# Golden_arduino_Updated.net
KiCad netlist of a schematic drawn in Altium Designer
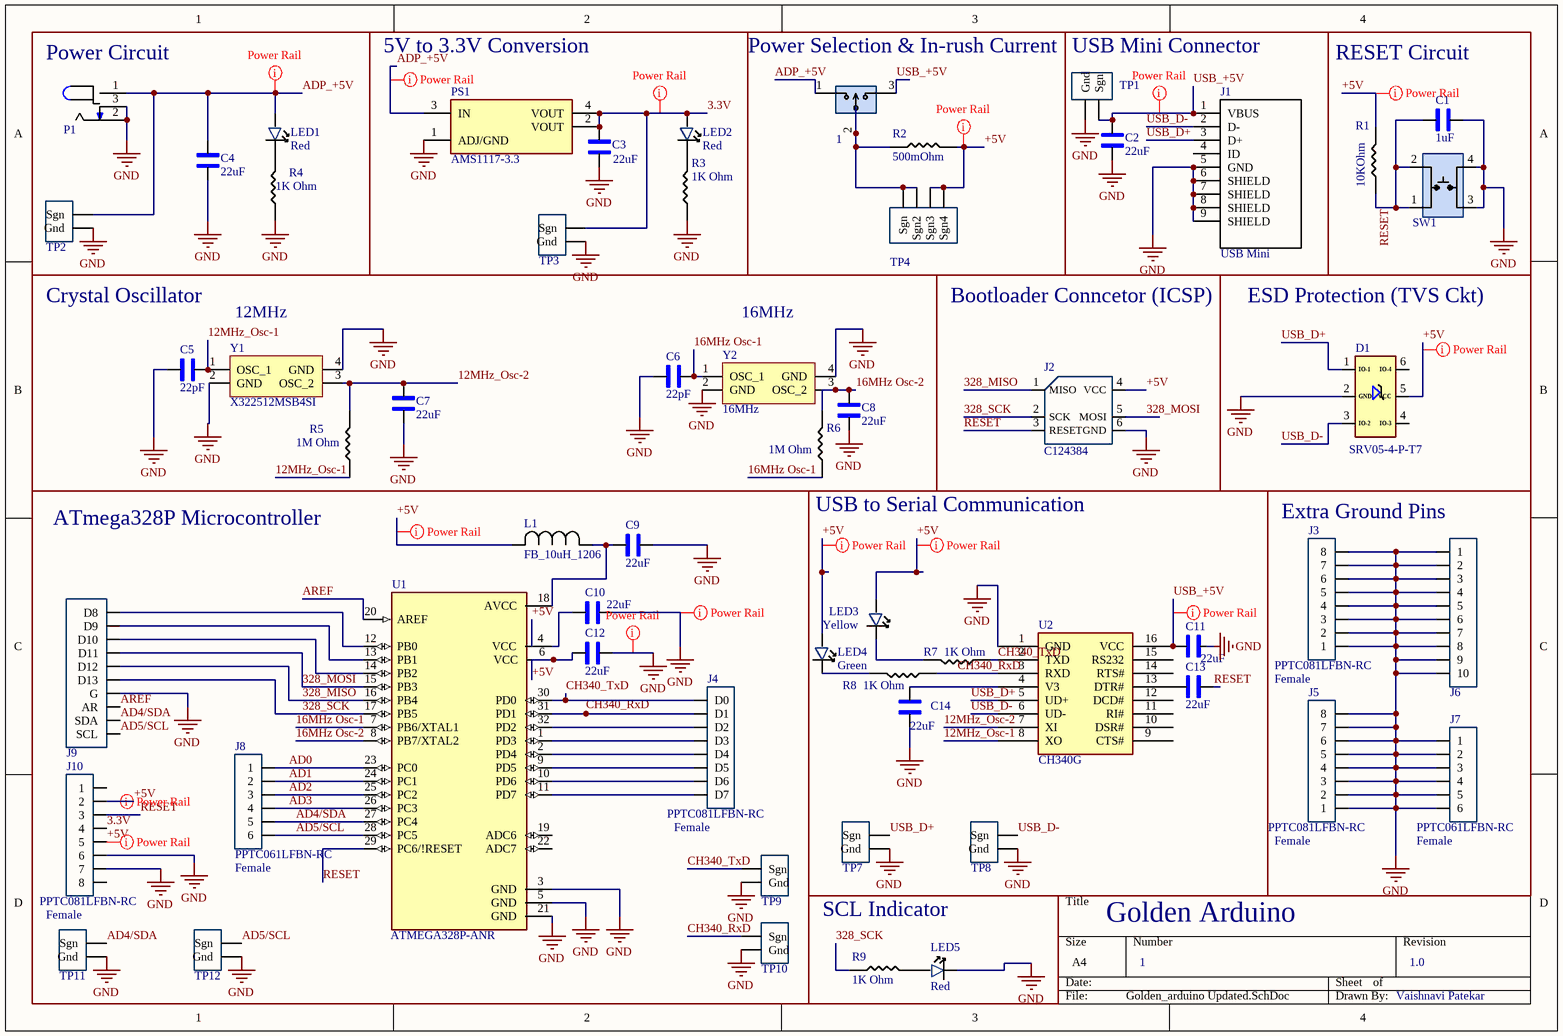
[diagram p0: Golden_arduino Updated.SchDoc]

(export (version "E")
  (design (tool "Eeschema 10.0.6"))
  (components
    (comp (ref "1")
      (value "PREC003SAAN-RC")
      (footprint "3_PIN_100mil")
      (description "Connector Header Through Hole 3 position 0.100\" (2.54mm)")
      (fields (field (name "LCSC PART#") "C49257"))
      (libsource (lib "ECEN5730Lib_2023_01_DS") (part "SW_3Pin_100mil_Switch"))
    )
    (comp (ref "C1")
      (value "1uF")
      (footprint "1206_Passive_Capacitor")
      (description "MULTILAYER CERAMIC CAPACITORS MLCC - SMD/SMT 1UF 50V 1206 ROHS")
      (fields (field (name "MFR PART #") "CL31B105KBHNNNE") (field (name "LCSC PART#") "C1848"))
      (libsource (lib "ECEN5730Lib_2023_01_DS") (part "C_1uF_1206"))
    )
    (comp (ref "C2")
      (value "22uF")
      (footprint "1206_Passive_Capacitor")
      (description "22uF ±10% 25V X5R 1206 Multilayer Ceramic Capacitors MLCC - SMD/SMT RoHS")
      (fields (field (name "MFR PART #") "CL31A226KAHNNNE") (field (name "LCSC PART#") "C12891"))
      (libsource (lib "ECEN5730Lib_2023_01_DS") (part "C_22uF_1206"))
    )
    (comp (ref "C3")
      (value "22uF")
      (footprint "1206_Passive_Capacitor")
      (description "22uF ±10% 25V X5R 1206 Multilayer Ceramic Capacitors MLCC - SMD/SMT RoHS")
      (fields (field (name "MFR PART #") "CL31A226KAHNNNE") (field (name "LCSC PART#") "C12891"))
      (libsource (lib "ECEN5730Lib_2023_01_DS") (part "C_22uF_1206"))
    )
    (comp (ref "C4")
      (value "22uF")
      (footprint "1206_Passive_Capacitor")
      (description "22uF ±10% 25V X5R 1206 Multilayer Ceramic Capacitors MLCC - SMD/SMT RoHS")
      (fields (field (name "MFR PART #") "CL31A226KAHNNNE") (field (name "LCSC PART#") "C12891"))
      (libsource (lib "ECEN5730Lib_2023_01_DS") (part "C_22uF_1206"))
    )
    (comp (ref "C5")
      (value "22pF")
      (footprint "1206_Passive_Capacitor")
      (description "22pF ±5% 1kV C0G 1206 Multilayer Ceramic Capacitors MLCC - SMD/SMT RoHS")
      (fields (field (name "LCSC PART#") "C313096") (field (name "MFR PART #") "1206CG220J102NT"))
      (libsource (lib "ECEN5730Lib_2023_01_DS") (part "C_22pF_1206"))
    )
    (comp (ref "C6")
      (value "22pF")
      (footprint "1206_Passive_Capacitor")
      (description "22pF ±5% 1kV C0G 1206 Multilayer Ceramic Capacitors MLCC - SMD/SMT RoHS")
      (fields (field (name "LCSC PART#") "C313096") (field (name "MFR PART #") "1206CG220J102NT"))
      (libsource (lib "ECEN5730Lib_2023_01_DS") (part "C_22pF_1206"))
    )
    (comp (ref "C7")
      (value "22uF")
      (footprint "1206_Passive_Capacitor")
      (description "22uF ±10% 25V X5R 1206 Multilayer Ceramic Capacitors MLCC - SMD/SMT RoHS")
      (fields (field (name "MFR PART #") "CL31A226KAHNNNE") (field (name "LCSC PART#") "C12891"))
      (libsource (lib "ECEN5730Lib_2023_01_DS") (part "C_22uF_1206"))
    )
    (comp (ref "C8")
      (value "22uF")
      (footprint "1206_Passive_Capacitor")
      (description "22uF ±10% 25V X5R 1206 Multilayer Ceramic Capacitors MLCC - SMD/SMT RoHS")
      (fields (field (name "MFR PART #") "CL31A226KAHNNNE") (field (name "LCSC PART#") "C12891"))
      (libsource (lib "ECEN5730Lib_2023_01_DS") (part "C_22uF_1206"))
    )
    (comp (ref "C9")
      (value "22uF")
      (footprint "1206_Passive_Capacitor")
      (description "22uF ±10% 25V X5R 1206 Multilayer Ceramic Capacitors MLCC - SMD/SMT RoHS")
      (fields (field (name "MFR PART #") "CL31A226KAHNNNE") (field (name "LCSC PART#") "C12891"))
      (libsource (lib "ECEN5730Lib_2023_01_DS") (part "C_22uF_1206"))
    )
    (comp (ref "C10")
      (value "22uF")
      (footprint "1206_Passive_Capacitor")
      (description "22uF ±10% 25V X5R 1206 Multilayer Ceramic Capacitors MLCC - SMD/SMT RoHS")
      (fields (field (name "MFR PART #") "CL31A226KAHNNNE") (field (name "LCSC PART#") "C12891"))
      (libsource (lib "ECEN5730Lib_2023_01_DS") (part "C_22uF_1206"))
    )
    (comp (ref "C11")
      (value "22uF")
      (footprint "1206_Passive_Capacitor")
      (description "22uF ±10% 25V X5R 1206 Multilayer Ceramic Capacitors MLCC - SMD/SMT RoHS")
      (fields (field (name "MFR PART #") "CL31A226KAHNNNE") (field (name "LCSC PART#") "C12891"))
      (libsource (lib "ECEN5730Lib_2023_01_DS") (part "C_22uF_1206"))
    )
    (comp (ref "C12")
      (value "22uF")
      (footprint "1206_Passive_Capacitor")
      (description "22uF ±10% 25V X5R 1206 Multilayer Ceramic Capacitors MLCC - SMD/SMT RoHS")
      (fields (field (name "MFR PART #") "CL31A226KAHNNNE") (field (name "LCSC PART#") "C12891"))
      (libsource (lib "ECEN5730Lib_2023_01_DS") (part "C_22uF_1206"))
    )
    (comp (ref "C13")
      (value "22uF")
      (footprint "1206_Passive_Capacitor")
      (description "22uF ±10% 25V X5R 1206 Multilayer Ceramic Capacitors MLCC - SMD/SMT RoHS")
      (fields (field (name "MFR PART #") "CL31A226KAHNNNE") (field (name "LCSC PART#") "C12891"))
      (libsource (lib "ECEN5730Lib_2023_01_DS") (part "C_22uF_1206"))
    )
    (comp (ref "C14")
      (value "22uF")
      (footprint "1206_Passive_Capacitor")
      (description "22uF ±10% 25V X5R 1206 Multilayer Ceramic Capacitors MLCC - SMD/SMT RoHS")
      (fields (field (name "MFR PART #") "CL31A226KAHNNNE") (field (name "LCSC PART#") "C12891"))
      (libsource (lib "ECEN5730Lib_2023_01_DS") (part "C_22uF_1206"))
    )
    (comp (ref "D1")
      (value "SRV05-4-P-T7")
      (footprint "TVS")
      (description "TVS SOT-23-6 ROHS")
      (fields (field (name "LCSC PART#") "C85364"))
      (libsource (lib "ECEN5730Lib_2023_01_DS") (part "D_TVS_Diode"))
    )
    (comp (ref "J1")
      (value "USB Mini")
      (footprint "USB_MINI_B")
      (description "Through Hole USB Connectors RoHS")
      (fields (field (name "LCSC PART#") "C46398") (field (name "MFR PART #") "920-462A2021D10102"))
      (libsource (lib "ECEN5730Lib_2023_01_DS") (part "J_USB_B_Mini"))
    )
    (comp (ref "J2")
      (value "NRPN032PAEN-RC")
      (footprint "ICSP")
      (description "Connector Header Through Hole 6 position 0.079\" (2.00mm)")
      (fields (field (name "LCSC PART#") "C124384"))
      (libsource (lib "ECEN5730Lib_2023_01_DS") (part "J_ICSP"))
    )
    (comp (ref "J3")
      (value "PPTC081LFBN-RC")
      (footprint "8_PIN_100MIL - Female")
      (description "8 Position Header Connector 0.100\" (2.54mm) Through Hole Tin")
      (fields (field (name "LCSC PART#") "C27438") (field (name "ALTIUM_VALUE") "Female"))
      (libsource (lib "ECEN5730Lib_2023_01_DS") (part "JF_8_PIN_FEMALE"))
    )
    (comp (ref "J4")
      (value "PPTC081LFBN-RC")
      (footprint "8_PIN_ARD-DIG_100MIL")
      (description "8 Position Header Connector 0.100\" (2.54mm) Through Hole Tin")
      (fields (field (name "LCSC PART#") "C27438") (field (name "ALTIUM_VALUE") "Female"))
      (libsource (lib "ECEN5730Lib_2023_01_DS") (part "JF_8_PIN_FEMALE_ARD-Dig"))
    )
    (comp (ref "J5")
      (value "PPTC081LFBN-RC")
      (footprint "8_PIN_100MIL - Female")
      (description "8 Position Header Connector 0.100\" (2.54mm) Through Hole Tin")
      (fields (field (name "LCSC PART#") "C27438") (field (name "ALTIUM_VALUE") "Female"))
      (libsource (lib "ECEN5730Lib_2023_01_DS") (part "JF_8_PIN_FEMALE"))
    )
    (comp (ref "J6")
      (value "PPTC101LFBN-RC")
      (footprint "10_PIN_100MIL - Female")
      (description "10 Position Header Connector 0.100\" (2.54mm) Through Hole Tin")
      (fields (field (name "LCSC PART#") "C225507"))
      (libsource (lib "ECEN5730Lib_2023_01_DS") (part "JF_10_PIN_FEMALE_"))
    )
    (comp (ref "J7")
      (value "PPTC061LFBN-RC")
      (footprint "6_PIN_100MIL -Female")
      (description "6 Position Header Connector 0.100\" (2.54mm) Through Hole Tin")
      (fields (field (name "LCSC PART#") "C40877") (field (name "ALTIUM_VALUE") "Female"))
      (libsource (lib "ECEN5730Lib_2023_01_DS") (part "JF_6_PIN_FEMALE"))
    )
    (comp (ref "J8")
      (value "PPTC061LFBN-RC")
      (footprint "6_PIN_100MIL -Female")
      (description "6 Position Header Connector 0.100\" (2.54mm) Through Hole Tin")
      (fields (field (name "LCSC PART#") "C40877") (field (name "ALTIUM_VALUE") "Female"))
      (libsource (lib "") (part "JF_6_PIN_FEMALE_1"))
    )
    (comp (ref "J9")
      (value "PPTC101LFBN-RC")
      (footprint "10_PIN_ARDUINO_100MIL")
      (description "10 Position Header Connector 0.100\" (2.54mm) Through Hole Tin")
      (fields (field (name "LCSC PART#") "C225507"))
      (libsource (lib "ECEN5730Lib_2023_01_DS") (part "JF_10_PIN_FEMALE_ARDUINO"))
    )
    (comp (ref "J10")
      (value "PPTC081LFBN-RC")
      (footprint "8_PIN_100MIL - Female")
      (description "8 Position Header Connector 0.100\" (2.54mm) Through Hole Tin")
      (fields (field (name "LCSC PART#") "C27438") (field (name "ALTIUM_VALUE") "Female"))
      (libsource (lib "") (part "JF_8_PIN_FEMALE_1"))
    )
    (comp (ref "L1")
      (value "FB_10uH_1206")
      (footprint "AIML-1206_ABR-M")
      (description "25mA 10uH ±10% 800mΩ 1206  Inductors (SMD) ROHS")
      (fields (field (name "MFR PART #") "CMI321609X100KT") (field (name "LCSC PART#") "C1051"))
      (libsource (lib "ECEN5730Lib_2023_01_DS") (part "FB_10uH_1206"))
    )
    (comp (ref "LED1")
      (value "Red")
      (footprint "LED_1206")
      (description "Red 621~631nm 1206 Light Emitting Diodes (LED) RoHS")
      (fields (field (name "MFR PART #") "15-21/R6C-FQ1R1B/2T") (field (name "LCSC PART#") "C93133"))
      (libsource (lib "ECEN5730Lib_2023_01_DS") (part "LED_RED_1206"))
    )
    (comp (ref "LED2")
      (value "Red")
      (footprint "LED_1206")
      (description "Red 621~631nm 1206 Light Emitting Diodes (LED) RoHS")
      (fields (field (name "MFR PART #") "15-21/R6C-FQ1R1B/2T") (field (name "LCSC PART#") "C93133"))
      (libsource (lib "ECEN5730Lib_2023_01_DS") (part "LED_RED_1206"))
    )
    (comp (ref "LED3")
      (value "Yellow")
      (footprint "LED_1206")
      (description "yellow 1206  Light Emitting Diodes (LED) ROHS")
      (fields (field (name "LCSC PART#") "C93094") (field (name "MFR PART #") "NCD1206Y1"))
      (libsource (lib "ECEN5730Lib_2023_01_DS") (part "LED_YELLOW_1206"))
    )
    (comp (ref "LED4")
      (value "Green")
      (footprint "LED_1206")
      (description "Green 513~528nm 1206 Light Emitting Diodes (LED) RoHS")
      (fields (field (name "MFR PART #") "SZYY1206G") (field (name "LCSC PART#") "C434439"))
      (libsource (lib "ECEN5730Lib_2023_01_DS") (part "LED_GREEN_1206"))
    )
    (comp (ref "LED5")
      (value "Red")
      (footprint "LED_1206")
      (description "Red 621~631nm 1206 Light Emitting Diodes (LED) RoHS")
      (fields (field (name "MFR PART #") "15-21/R6C-FQ1R1B/2T") (field (name "LCSC PART#") "C93133"))
      (libsource (lib "ECEN5730Lib_2023_01_DS") (part "LED_RED_1206"))
    )
    (comp (ref "P1")
      (value "Power Jack")
      (footprint "Power_Jack")
      (description "Power Barrel Connector Jack 2.10mm ID (0.083\"), 5.50mm OD (0.217\") Through Hole, Right Angle")
      (fields (field (name "MFR PART #") "PJ-102A") (field (name "LCSC PART#") "C136744"))
      (libsource (lib "ECEN5730Lib_2023_01_DS") (part "P_Power Jack"))
    )
    (comp (ref "PS1")
      (value "AMS1117-3.3")
      (footprint "LDO")
      (description "LOW DROPOUT REGULATORS(LDO) POSITIVE FIXED 1.3V @ 800MA 15V 3.3V 1A SOT-223 ROHS")
      (fields (field (name "LCSC PART#") "C6186"))
      (libsource (lib "ECEN5730Lib_2023_01_DS") (part "PS_AMS_LDO_3v3"))
    )
    (comp (ref "R1")
      (value "10KOhm")
      (footprint "1206_Passive_Resitor")
      (description "10 kOhms ±5% 0.25W, 1/4W Chip Resistor 1206 (3216 Metric) Automotive AEC-Q200 Thick Film")
      (fields (field (name "MFR PART #") "RMCF1206FT10K0") (field (name "LCSC PART#") "C17902"))
      (libsource (lib "ECEN5730Lib_2023_01_DS") (part "R_10KOhm_1206"))
    )
    (comp (ref "R2")
      (value "500mOhm")
      (footprint "1206_Passive_Resitor")
      (description "Resistors/Shunt 250mW 500mΩ ±800ppm/℃ ±5% 1206  Current Sense  Resistors ROHS")
      (fields (field (name "MFR PART #") "1206W4J050KT5E") (field (name "LCSC PART#") "C247433"))
      (libsource (lib "ECEN5730Lib_2023_01_DS") (part "R_500mOhm_1206"))
    )
    (comp (ref "R3")
      (value "1K Ohm")
      (footprint "1206_Passive_Resitor")
      (description "CHIP RESISTOR - SURFACE MOUNT 1KOHMS ±1% 1/4W 1206 ROHS")
      (fields (field (name "MFR PART #") "RNCP1206FTD1K00CT") (field (name "LCSC PART#") "C4410"))
      (libsource (lib "ECEN5730Lib_2023_01_DS") (part "R_1K_1206"))
    )
    (comp (ref "R4")
      (value "1K Ohm")
      (footprint "1206_Passive_Resitor")
      (description "CHIP RESISTOR - SURFACE MOUNT 1KOHMS ±1% 1/4W 1206 ROHS")
      (fields (field (name "MFR PART #") "RNCP1206FTD1K00CT") (field (name "LCSC PART#") "C4410"))
      (libsource (lib "ECEN5730Lib_2023_01_DS") (part "R_1K_1206"))
    )
    (comp (ref "R5")
      (value "1M Ohm")
      (footprint "1206_Passive_Resitor")
      (description "CHIP RESISTOR - SURFACE MOUNT 1MOHMS ±1% 1/4W 1206 ROHS")
      (fields (field (name "MFR PART #") "RMCF1206JT1M00") (field (name "LCSC PART#") "C17927"))
      (libsource (lib "ECEN5730Lib_2023_01_DS") (part "R_1M_1206"))
    )
    (comp (ref "R6")
      (value "1M Ohm")
      (footprint "1206_Passive_Resitor")
      (description "CHIP RESISTOR - SURFACE MOUNT 1MOHMS ±1% 1/4W 1206 ROHS")
      (fields (field (name "MFR PART #") "RMCF1206JT1M00") (field (name "LCSC PART#") "C17927"))
      (libsource (lib "ECEN5730Lib_2023_01_DS") (part "R_1M_1206"))
    )
    (comp (ref "R7")
      (value "1K Ohm")
      (footprint "1206_Passive_Resitor")
      (description "CHIP RESISTOR - SURFACE MOUNT 1KOHMS ±1% 1/4W 1206 ROHS")
      (fields (field (name "MFR PART #") "RNCP1206FTD1K00CT") (field (name "LCSC PART#") "C4410"))
      (libsource (lib "ECEN5730Lib_2023_01_DS") (part "R_1K_1206"))
    )
    (comp (ref "R8")
      (value "1K Ohm")
      (footprint "1206_Passive_Resitor")
      (description "CHIP RESISTOR - SURFACE MOUNT 1KOHMS ±1% 1/4W 1206 ROHS")
      (fields (field (name "MFR PART #") "RNCP1206FTD1K00CT") (field (name "LCSC PART#") "C4410"))
      (libsource (lib "ECEN5730Lib_2023_01_DS") (part "R_1K_1206"))
    )
    (comp (ref "R9")
      (value "1K Ohm")
      (footprint "1206_Passive_Resitor")
      (description "CHIP RESISTOR - SURFACE MOUNT 1KOHMS ±1% 1/4W 1206 ROHS")
      (fields (field (name "MFR PART #") "RNCP1206FTD1K00CT") (field (name "LCSC PART#") "C4410"))
      (libsource (lib "ECEN5730Lib_2023_01_DS") (part "R_1K_1206"))
    )
    (comp (ref "SW1")
      (value "TL3305AF160QG")
      (footprint "Switch_JLC")
      (description "Tactile Switch SPST-NO Top Actuated Surface Mount")
      (fields (field (name "MFR PART #") "KH-4.5X4.5X4.3H-STM") (field (name "LCSC PART#") "C2837550"))
      (libsource (lib "ECEN5730Lib_2023_01_DS") (part "SW_Push_Button_JLC"))
    )
    (comp (ref "TP1")
      (value "10x Probe TP")
      (footprint "TP10x_Probe")
      (description "Test Point 300 mil centers")
      (libsource (lib "") (part "TP_10x_Probe_1"))
    )
    (comp (ref "TP2")
      (value "10x Probe TP")
      (footprint "TP10x_Probe")
      (description "Test Point 300 mil centers")
      (libsource (lib "ECEN5730Lib_2023_01_DS") (part "TP_10x_Probe"))
    )
    (comp (ref "TP3")
      (value "10x Probe TP")
      (footprint "TP10x_Probe")
      (description "Test Point 300 mil centers")
      (libsource (lib "ECEN5730Lib_2023_01_DS") (part "TP_10x_Probe"))
    )
    (comp (ref "TP4")
      (value "10x Probe Floating TP")
      (footprint "TP10x_Floating")
      (description "Test Point 300 mil centers")
      (libsource (lib "ECEN5730Lib_2023_01_DS") (part "TP_10x_Floating"))
    )
    (comp (ref "TP7")
      (value "10x Probe TP")
      (footprint "TP10x_Probe")
      (description "Test Point 300 mil centers")
      (libsource (lib "ECEN5730Lib_2023_01_DS") (part "TP_10x_Probe"))
    )
    (comp (ref "TP8")
      (value "10x Probe TP")
      (footprint "TP10x_Probe")
      (description "Test Point 300 mil centers")
      (libsource (lib "ECEN5730Lib_2023_01_DS") (part "TP_10x_Probe"))
    )
    (comp (ref "TP9")
      (value "10x Probe TP")
      (footprint "TP10x_Probe")
      (description "Test Point 300 mil centers")
      (libsource (lib "") (part "TP_10x_Probe_1"))
    )
    (comp (ref "TP10")
      (value "10x Probe TP")
      (footprint "TP10x_Probe")
      (description "Test Point 300 mil centers")
      (libsource (lib "") (part "TP_10x_Probe_1"))
    )
    (comp (ref "TP11")
      (value "10x Probe TP")
      (footprint "TP10x_Probe")
      (description "Test Point 300 mil centers")
      (libsource (lib "ECEN5730Lib_2023_01_DS") (part "TP_10x_Probe"))
    )
    (comp (ref "TP12")
      (value "10x Probe TP")
      (footprint "TP10x_Probe")
      (description "Test Point 300 mil centers")
      (libsource (lib "ECEN5730Lib_2023_01_DS") (part "TP_10x_Probe"))
    )
    (comp (ref "U1")
      (value "ATMEGA328P-ANR")
      (footprint "ATMega328P")
      (description "AVR AVR® ATmega Microcontroller IC 8-Bit 20MHz 32KB (16K x 16) FLASH 32-TQFP (7x7)")
      (fields (field (name "MFR PART #") "ATMEGA328P-AU") (field (name "LCSC PART#") "C14877"))
      (libsource (lib "ECEN5730Lib_2023_01_DS") (part "U_ATMega328P"))
    )
    (comp (ref "U2")
      (value "CH340G")
      (footprint "USB to serial")
      (description "Transceiver USB 2.0 2Mbps SOP-16_150mil USB ICs RoHS")
      (fields (field (name "LCSC PART#") "C14267"))
      (libsource (lib "ECEN5730Lib_2023_01_DS") (part "U_USBtoSerial"))
    )
    (comp (ref "Y1")
      (value "X322512MSB4SI")
      (footprint "Crystal resonator")
      (description "SMD Crystal Resonators 12MHz ±10ppm SMD-3225_4P RoHS")
      (fields (field (name "LCSC PART#") "C9002"))
      (libsource (lib "ECEN5730Lib_2023_01_DS") (part "X_12MHz_Res"))
    )
    (comp (ref "Y2")
      (value "16MHz")
      (footprint "Crystal resonator")
      (description "±10ppm 16000000Hz -40℃~85℃ 贴片无源晶振 60Ω 9pF SMD3225-4P Crystals ROHS")
      (fields (field (name "LCSC PART#") "C13738") (field (name "MFR PART #") "X322516MLB4SI"))
      (libsource (lib "ECEN5730Lib_2023_01_DS") (part "X_16Mhz_Res"))
    )
  )
  (nets
    (net (code "1") (name "/+5V") (class "Default")
      (node (ref "C12") (pin "2") (pinfunction "2_2") (pintype "passive"))
      (node (ref "D1") (pin "5") (pinfunction "VCC_5") (pintype "passive"))
      (node (ref "J10") (pin "2") (pinfunction "2_2") (pintype "passive"))
      (node (ref "J10") (pin "5") (pinfunction "5_5") (pintype "passive"))
      (node (ref "J2") (pin "4") (pinfunction "VCC_4") (pintype "passive"))
      (node (ref "L1") (pin "2") (pinfunction "2_2") (pintype "passive"))
      (node (ref "LED3") (pin "1") (pinfunction "1_1") (pintype "passive"))
      (node (ref "LED4") (pin "1") (pinfunction "1_1") (pintype "passive"))
      (node (ref "R1") (pin "2") (pinfunction "2_2") (pintype "passive"))
      (node (ref "R2") (pin "2") (pinfunction "2_2") (pintype "passive"))
      (node (ref "TP4") (pin "3") (pinfunction "Sgn3_3") (pintype "passive"))
      (node (ref "TP4") (pin "4") (pinfunction "Sgn4_4") (pintype "passive"))
      (node (ref "U1") (pin "6") (pinfunction "VCC_6") (pintype "power_in"))
    )
    (net (code "2") (name "/3.3V") (class "Default")
      (node (ref "C3") (pin "2") (pinfunction "2_2") (pintype "passive"))
      (node (ref "J10") (pin "4") (pinfunction "4_4") (pintype "passive"))
      (node (ref "LED2") (pin "1") (pinfunction "1_1") (pintype "passive"))
      (node (ref "PS1") (pin "2") (pinfunction "VOUT_2") (pintype "power_in"))
      (node (ref "PS1") (pin "4") (pinfunction "VOUT_4") (pintype "power_in"))
      (node (ref "TP3") (pin "1") (pinfunction "Sgn_1") (pintype "passive"))
    )
    (net (code "3") (name "/12MHz_Osc-1") (class "Default")
      (node (ref "C5") (pin "2") (pinfunction "2_2") (pintype "passive"))
      (node (ref "R5") (pin "1") (pinfunction "1_1") (pintype "passive"))
      (node (ref "U2") (pin "8") (pinfunction "XO_8") (pintype "passive"))
      (node (ref "Y1") (pin "1") (pinfunction "OSC_1_1") (pintype "passive"))
    )
    (net (code "4") (name "/12MHz_Osc-2") (class "Default")
      (node (ref "C7") (pin "2") (pinfunction "2_2") (pintype "passive"))
      (node (ref "R5") (pin "2") (pinfunction "2_2") (pintype "passive"))
      (node (ref "U2") (pin "7") (pinfunction "XI_7") (pintype "passive"))
      (node (ref "Y1") (pin "3") (pinfunction "OSC_2_3") (pintype "passive"))
    )
    (net (code "5") (name "/16MHz Osc-1") (class "Default")
      (node (ref "C6") (pin "2") (pinfunction "2_2") (pintype "passive"))
      (node (ref "R6") (pin "1") (pinfunction "1_1") (pintype "passive"))
      (node (ref "U1") (pin "7") (pinfunction "PB6/XTAL1_7") (pintype "bidirectional"))
      (node (ref "Y2") (pin "1") (pinfunction "OSC_1_1") (pintype "passive"))
    )
    (net (code "6") (name "/16MHz Osc-2") (class "Default")
      (node (ref "C8") (pin "2") (pinfunction "2_2") (pintype "passive"))
      (node (ref "R6") (pin "2") (pinfunction "2_2") (pintype "passive"))
      (node (ref "U1") (pin "8") (pinfunction "PB7/XTAL2_8") (pintype "bidirectional"))
      (node (ref "Y2") (pin "3") (pinfunction "OSC_2_3") (pintype "passive"))
    )
    (net (code "7") (name "/328_MISO") (class "Default")
      (node (ref "J2") (pin "1") (pinfunction "MISO_1") (pintype "passive"))
      (node (ref "J9") (pin "6") (pinfunction "D12_6") (pintype "passive"))
      (node (ref "U1") (pin "16") (pinfunction "PB4_16") (pintype "bidirectional"))
    )
    (net (code "8") (name "/328_MOSI") (class "Default")
      (node (ref "J2") (pin "5") (pinfunction "MOSI_5") (pintype "passive"))
      (node (ref "J9") (pin "7") (pinfunction "D11_7") (pintype "passive"))
      (node (ref "U1") (pin "15") (pinfunction "PB3_15") (pintype "bidirectional"))
    )
    (net (code "9") (name "/328_SCK") (class "Default")
      (node (ref "J2") (pin "2") (pinfunction "SCK_2") (pintype "passive"))
      (node (ref "J9") (pin "5") (pinfunction "D13_5") (pintype "passive"))
      (node (ref "R9") (pin "1") (pinfunction "1_1") (pintype "passive"))
      (node (ref "U1") (pin "17") (pinfunction "PB5_17") (pintype "bidirectional"))
    )
    (net (code "10") (name "/AD0") (class "Default")
      (node (ref "J8") (pin "1") (pinfunction "1_1") (pintype "passive"))
      (node (ref "U1") (pin "23") (pinfunction "PC0_23") (pintype "bidirectional"))
    )
    (net (code "11") (name "/AD1") (class "Default")
      (node (ref "J8") (pin "2") (pinfunction "2_2") (pintype "passive"))
      (node (ref "U1") (pin "24") (pinfunction "PC1_24") (pintype "bidirectional"))
    )
    (net (code "12") (name "/AD2") (class "Default")
      (node (ref "J8") (pin "3") (pinfunction "3_3") (pintype "passive"))
      (node (ref "U1") (pin "25") (pinfunction "PC2_25") (pintype "bidirectional"))
    )
    (net (code "13") (name "/AD3") (class "Default")
      (node (ref "J8") (pin "4") (pinfunction "4_4") (pintype "passive"))
      (node (ref "U1") (pin "26") (pinfunction "PC3_26") (pintype "bidirectional"))
    )
    (net (code "14") (name "/AD4{slash}SDA") (class "Default")
      (node (ref "J8") (pin "5") (pinfunction "5_5") (pintype "passive"))
      (node (ref "J9") (pin "2") (pinfunction "SDA_2") (pintype "passive"))
      (node (ref "TP11") (pin "1") (pinfunction "Sgn_1") (pintype "passive"))
      (node (ref "U1") (pin "27") (pinfunction "PC4_27") (pintype "bidirectional"))
    )
    (net (code "15") (name "/AD5{slash}SCL") (class "Default")
      (node (ref "J8") (pin "6") (pinfunction "6_6") (pintype "passive"))
      (node (ref "J9") (pin "1") (pinfunction "SCL_1") (pintype "passive"))
      (node (ref "TP12") (pin "1") (pinfunction "Sgn_1") (pintype "passive"))
      (node (ref "U1") (pin "28") (pinfunction "PC5_28") (pintype "bidirectional"))
    )
    (net (code "16") (name "/ADP_+5V") (class "Default")
      (node (ref "1") (pin "1") (pinfunction "1_1") (pintype "passive"))
      (node (ref "C4") (pin "2") (pinfunction "2_2") (pintype "passive"))
      (node (ref "LED1") (pin "1") (pinfunction "1_1") (pintype "passive"))
      (node (ref "P1") (pin "1") (pinfunction "1_1") (pintype "power_in"))
      (node (ref "PS1") (pin "3") (pinfunction "IN_3") (pintype "power_in"))
      (node (ref "TP2") (pin "1") (pinfunction "Sgn_1") (pintype "passive"))
    )
    (net (code "17") (name "/AREF") (class "Default")
      (node (ref "J9") (pin "3") (pinfunction "AR_3") (pintype "passive"))
      (node (ref "U1") (pin "20") (pinfunction "AREF_20") (pintype "input"))
    )
    (net (code "18") (name "/CH340_RxD") (class "Default")
      (node (ref "J4") (pin "7") (pinfunction "D1_7") (pintype "passive"))
      (node (ref "R8") (pin "1") (pinfunction "1_1") (pintype "passive"))
      (node (ref "TP10") (pin "1") (pinfunction "Sgn_1") (pintype "passive"))
      (node (ref "U1") (pin "31") (pinfunction "PD1_31") (pintype "bidirectional"))
      (node (ref "U2") (pin "3") (pinfunction "RXD_3") (pintype "passive"))
    )
    (net (code "19") (name "/CH340_TxD") (class "Default")
      (node (ref "J4") (pin "8") (pinfunction "D0_8") (pintype "passive"))
      (node (ref "R7") (pin "1") (pinfunction "1_1") (pintype "passive"))
      (node (ref "TP9") (pin "1") (pinfunction "Sgn_1") (pintype "passive"))
      (node (ref "U1") (pin "30") (pinfunction "PD0_30") (pintype "bidirectional"))
      (node (ref "U2") (pin "2") (pinfunction "TXD_2") (pintype "passive"))
    )
    (net (code "20") (name "/RESET") (class "Default")
      (node (ref "C1") (pin "1") (pinfunction "1_1") (pintype "passive"))
      (node (ref "C13") (pin "1") (pinfunction "1_1") (pintype "passive"))
      (node (ref "J10") (pin "3") (pinfunction "3_3") (pintype "passive"))
      (node (ref "J2") (pin "3") (pinfunction "RESET_3") (pintype "passive"))
      (node (ref "R1") (pin "1") (pinfunction "1_1") (pintype "passive"))
      (node (ref "SW1") (pin "1") (pinfunction "1_1") (pintype "passive"))
      (node (ref "SW1") (pin "2") (pinfunction "2_2") (pintype "passive"))
      (node (ref "U1") (pin "29") (pinfunction "PC6/!RESET_29") (pintype "bidirectional"))
    )
    (net (code "21") (name "/USB_+5V") (class "Default")
      (node (ref "1") (pin "3") (pinfunction "3_3") (pintype "passive"))
      (node (ref "C11") (pin "2") (pinfunction "2_2") (pintype "passive"))
      (node (ref "C2") (pin "2") (pinfunction "2_2") (pintype "passive"))
      (node (ref "J1") (pin "1") (pinfunction "VBUS_1") (pintype "passive"))
      (node (ref "TP1") (pin "1") (pinfunction "Sgn_1") (pintype "passive"))
      (node (ref "U2") (pin "16") (pinfunction "VCC_16") (pintype "passive"))
    )
    (net (code "22") (name "/USB_D+") (class "Default")
      (node (ref "D1") (pin "1") (pinfunction "IO-1_1") (pintype "passive"))
      (node (ref "J1") (pin "3") (pinfunction "D+_3") (pintype "passive"))
      (node (ref "TP7") (pin "1") (pinfunction "Sgn_1") (pintype "passive"))
      (node (ref "U2") (pin "5") (pinfunction "UD+_5") (pintype "passive"))
    )
    (net (code "23") (name "/USB_D-") (class "Default")
      (node (ref "D1") (pin "3") (pinfunction "IO-2_3") (pintype "passive"))
      (node (ref "J1") (pin "2") (pinfunction "D-_2") (pintype "passive"))
      (node (ref "TP8") (pin "1") (pinfunction "Sgn_1") (pintype "passive"))
      (node (ref "U2") (pin "6") (pinfunction "UD-_6") (pintype "passive"))
    )
    (net (code "24") (name "GND") (class "Default")
      (node (ref "C1") (pin "2") (pinfunction "2_2") (pintype "passive"))
      (node (ref "C10") (pin "1") (pinfunction "1_1") (pintype "passive"))
      (node (ref "C11") (pin "1") (pinfunction "1_1") (pintype "passive"))
      (node (ref "C12") (pin "1") (pinfunction "1_1") (pintype "passive"))
      (node (ref "C14") (pin "2") (pinfunction "2_2") (pintype "passive"))
      (node (ref "C2") (pin "1") (pinfunction "1_1") (pintype "passive"))
      (node (ref "C3") (pin "1") (pinfunction "1_1") (pintype "passive"))
      (node (ref "C4") (pin "1") (pinfunction "1_1") (pintype "passive"))
      (node (ref "C5") (pin "1") (pinfunction "1_1") (pintype "passive"))
      (node (ref "C6") (pin "1") (pinfunction "1_1") (pintype "passive"))
      (node (ref "C7") (pin "1") (pinfunction "1_1") (pintype "passive"))
      (node (ref "C8") (pin "1") (pinfunction "1_1") (pintype "passive"))
      (node (ref "C9") (pin "1") (pinfunction "1_1") (pintype "passive"))
      (node (ref "D1") (pin "2") (pinfunction "GND_2") (pintype "passive"))
      (node (ref "J1") (pin "5") (pinfunction "GND_5") (pintype "passive"))
      (node (ref "J1") (pin "6") (pinfunction "SHIELD_6") (pintype "passive"))
      (node (ref "J1") (pin "7") (pinfunction "SHIELD_7") (pintype "passive"))
      (node (ref "J1") (pin "8") (pinfunction "SHIELD_8") (pintype "passive"))
      (node (ref "J1") (pin "9") (pinfunction "SHIELD_9") (pintype "passive"))
      (node (ref "J10") (pin "6") (pinfunction "6_6") (pintype "passive"))
      (node (ref "J10") (pin "7") (pinfunction "7_7") (pintype "passive"))
      (node (ref "J2") (pin "6") (pinfunction "GND_6") (pintype "passive"))
      (node (ref "J3") (pin "1") (pinfunction "1_1") (pintype "passive"))
      (node (ref "J3") (pin "2") (pinfunction "2_2") (pintype "passive"))
      (node (ref "J3") (pin "3") (pinfunction "3_3") (pintype "passive"))
      (node (ref "J3") (pin "4") (pinfunction "4_4") (pintype "passive"))
      (node (ref "J3") (pin "5") (pinfunction "5_5") (pintype "passive"))
      (node (ref "J3") (pin "6") (pinfunction "6_6") (pintype "passive"))
      (node (ref "J3") (pin "7") (pinfunction "7_7") (pintype "passive"))
      (node (ref "J3") (pin "8") (pinfunction "8_8") (pintype "passive"))
      (node (ref "J5") (pin "1") (pinfunction "1_1") (pintype "passive"))
      (node (ref "J5") (pin "2") (pinfunction "2_2") (pintype "passive"))
      (node (ref "J5") (pin "3") (pinfunction "3_3") (pintype "passive"))
      (node (ref "J5") (pin "4") (pinfunction "4_4") (pintype "passive"))
      (node (ref "J5") (pin "5") (pinfunction "5_5") (pintype "passive"))
      (node (ref "J5") (pin "6") (pinfunction "6_6") (pintype "passive"))
      (node (ref "J5") (pin "7") (pinfunction "7_7") (pintype "passive"))
      (node (ref "J5") (pin "8") (pinfunction "8_8") (pintype "passive"))
      (node (ref "J6") (pin "1") (pinfunction "1_1") (pintype "passive"))
      (node (ref "J6") (pin "10") (pinfunction "10_10") (pintype "passive"))
      (node (ref "J6") (pin "2") (pinfunction "2_2") (pintype "passive"))
      (node (ref "J6") (pin "3") (pinfunction "3_3") (pintype "passive"))
      (node (ref "J6") (pin "4") (pinfunction "4_4") (pintype "passive"))
      (node (ref "J6") (pin "5") (pinfunction "5_5") (pintype "passive"))
      (node (ref "J6") (pin "6") (pinfunction "6_6") (pintype "passive"))
      (node (ref "J6") (pin "7") (pinfunction "7_7") (pintype "passive"))
      (node (ref "J6") (pin "8") (pinfunction "8_8") (pintype "passive"))
      (node (ref "J6") (pin "9") (pinfunction "9_9") (pintype "passive"))
      (node (ref "J7") (pin "1") (pinfunction "1_1") (pintype "passive"))
      (node (ref "J7") (pin "2") (pinfunction "2_2") (pintype "passive"))
      (node (ref "J7") (pin "3") (pinfunction "3_3") (pintype "passive"))
      (node (ref "J7") (pin "4") (pinfunction "4_4") (pintype "passive"))
      (node (ref "J7") (pin "5") (pinfunction "5_5") (pintype "passive"))
      (node (ref "J7") (pin "6") (pinfunction "6_6") (pintype "passive"))
      (node (ref "J9") (pin "4") (pinfunction "G_4") (pintype "passive"))
      (node (ref "LED5") (pin "2") (pinfunction "2_2") (pintype "passive"))
      (node (ref "P1") (pin "2") (pinfunction "2_2") (pintype "power_in"))
      (node (ref "P1") (pin "3") (pinfunction "3_3") (pintype "power_in"))
      (node (ref "PS1") (pin "1") (pinfunction "ADJ/GND_1") (pintype "passive"))
      (node (ref "R3") (pin "1") (pinfunction "1_1") (pintype "passive"))
      (node (ref "R4") (pin "1") (pinfunction "1_1") (pintype "passive"))
      (node (ref "SW1") (pin "3") (pinfunction "3_3") (pintype "passive"))
      (node (ref "SW1") (pin "4") (pinfunction "4_4") (pintype "passive"))
      (node (ref "TP1") (pin "2") (pinfunction "Gnd_2") (pintype "passive"))
      (node (ref "TP10") (pin "2") (pinfunction "Gnd_2") (pintype "passive"))
      (node (ref "TP11") (pin "2") (pinfunction "Gnd_2") (pintype "passive"))
      (node (ref "TP12") (pin "2") (pinfunction "Gnd_2") (pintype "passive"))
      (node (ref "TP2") (pin "2") (pinfunction "Gnd_2") (pintype "passive"))
      (node (ref "TP3") (pin "2") (pinfunction "Gnd_2") (pintype "passive"))
      (node (ref "TP7") (pin "2") (pinfunction "Gnd_2") (pintype "passive"))
      (node (ref "TP8") (pin "2") (pinfunction "Gnd_2") (pintype "passive"))
      (node (ref "TP9") (pin "2") (pinfunction "Gnd_2") (pintype "passive"))
      (node (ref "U1") (pin "21") (pinfunction "GND_21") (pintype "power_in"))
      (node (ref "U1") (pin "3") (pinfunction "GND_3") (pintype "power_in"))
      (node (ref "U1") (pin "5") (pinfunction "GND_5") (pintype "power_in"))
      (node (ref "U2") (pin "1") (pinfunction "GND_1") (pintype "passive"))
      (node (ref "Y1") (pin "2") (pinfunction "GND_2") (pintype "passive"))
      (node (ref "Y1") (pin "4") (pinfunction "GND_4") (pintype "passive"))
      (node (ref "Y2") (pin "2") (pinfunction "GND_2") (pintype "passive"))
      (node (ref "Y2") (pin "4") (pinfunction "GND_4") (pintype "passive"))
    )
    (net (code "25") (name "Net-(C10-Pad2)") (class "Default")
      (node (ref "C10") (pin "2") (pinfunction "2_2") (pintype "passive"))
      (node (ref "U1") (pin "4") (pinfunction "VCC_4") (pintype "power_in"))
    )
    (net (code "26") (name "Net-(J4-D2)") (class "Default")
      (node (ref "J4") (pin "6") (pinfunction "D2_6") (pintype "passive"))
      (node (ref "U1") (pin "32") (pinfunction "PD2_32") (pintype "bidirectional"))
    )
    (net (code "27") (name "Net-(J4-D3)") (class "Default")
      (node (ref "J4") (pin "5") (pinfunction "D3_5") (pintype "passive"))
      (node (ref "U1") (pin "1") (pinfunction "PD3_1") (pintype "bidirectional"))
    )
    (net (code "28") (name "Net-(J4-D4)") (class "Default")
      (node (ref "J4") (pin "4") (pinfunction "D4_4") (pintype "passive"))
      (node (ref "U1") (pin "2") (pinfunction "PD4_2") (pintype "bidirectional"))
    )
    (net (code "29") (name "Net-(J4-D5)") (class "Default")
      (node (ref "J4") (pin "3") (pinfunction "D5_3") (pintype "passive"))
      (node (ref "U1") (pin "9") (pinfunction "PD5_9") (pintype "bidirectional"))
    )
    (net (code "30") (name "Net-(J4-D6)") (class "Default")
      (node (ref "J4") (pin "2") (pinfunction "D6_2") (pintype "passive"))
      (node (ref "U1") (pin "10") (pinfunction "PD6_10") (pintype "bidirectional"))
    )
    (net (code "31") (name "Net-(J4-D7)") (class "Default")
      (node (ref "J4") (pin "1") (pinfunction "D7_1") (pintype "passive"))
      (node (ref "U1") (pin "11") (pinfunction "PD7_11") (pintype "bidirectional"))
    )
    (net (code "32") (name "Net-(J9-D8)") (class "Default")
      (node (ref "J9") (pin "10") (pinfunction "D8_10") (pintype "passive"))
      (node (ref "U1") (pin "12") (pinfunction "PB0_12") (pintype "bidirectional"))
    )
    (net (code "33") (name "Net-(J9-D9)") (class "Default")
      (node (ref "J9") (pin "9") (pinfunction "D9_9") (pintype "passive"))
      (node (ref "U1") (pin "13") (pinfunction "PB1_13") (pintype "bidirectional"))
    )
    (net (code "34") (name "Net-(J9-D10)") (class "Default")
      (node (ref "J9") (pin "8") (pinfunction "D10_8") (pintype "passive"))
      (node (ref "U1") (pin "14") (pinfunction "PB2_14") (pintype "bidirectional"))
    )
    (net (code "35") (name "Net-(LED1-Pad2)") (class "Default")
      (node (ref "LED1") (pin "2") (pinfunction "2_2") (pintype "passive"))
      (node (ref "R4") (pin "2") (pinfunction "2_2") (pintype "passive"))
    )
    (net (code "36") (name "Net-(LED2-Pad2)") (class "Default")
      (node (ref "LED2") (pin "2") (pinfunction "2_2") (pintype "passive"))
      (node (ref "R3") (pin "2") (pinfunction "2_2") (pintype "passive"))
    )
    (net (code "37") (name "Net-(LED3-Pad2)") (class "Default")
      (node (ref "LED3") (pin "2") (pinfunction "2_2") (pintype "passive"))
      (node (ref "R7") (pin "2") (pinfunction "2_2") (pintype "passive"))
    )
    (net (code "38") (name "Net-(LED4-Pad2)") (class "Default")
      (node (ref "LED4") (pin "2") (pinfunction "2_2") (pintype "passive"))
      (node (ref "R8") (pin "2") (pinfunction "2_2") (pintype "passive"))
    )
    (net (code "39") (name "Net-(LED5-Pad1)") (class "Default")
      (node (ref "LED5") (pin "1") (pinfunction "1_1") (pintype "passive"))
      (node (ref "R9") (pin "2") (pinfunction "2_2") (pintype "passive"))
    )
    (net (code "40") (name "Net-(TP4-Sgn)") (class "Default")
      (node (ref "1") (pin "2") (pinfunction "2_2") (pintype "passive"))
      (node (ref "R2") (pin "1") (pinfunction "1_1") (pintype "passive"))
      (node (ref "TP4") (pin "1") (pinfunction "Sgn_1") (pintype "passive"))
      (node (ref "TP4") (pin "2") (pinfunction "Sgn2_2") (pintype "passive"))
    )
    (net (code "41") (name "Net-(U1-AVCC)") (class "Default")
      (node (ref "C9") (pin "2") (pinfunction "2_2") (pintype "passive"))
      (node (ref "L1") (pin "1") (pinfunction "1_1") (pintype "passive"))
      (node (ref "U1") (pin "18") (pinfunction "AVCC_18") (pintype "power_in"))
    )
    (net (code "42") (name "Net-(U2-DTR#)") (class "Default")
      (node (ref "C13") (pin "2") (pinfunction "2_2") (pintype "passive"))
      (node (ref "U2") (pin "13") (pinfunction "DTR#_13") (pintype "passive"))
    )
    (net (code "43") (name "Net-(U2-V3)") (class "Default")
      (node (ref "C14") (pin "1") (pinfunction "1_1") (pintype "passive"))
      (node (ref "U2") (pin "4") (pinfunction "V3_4") (pintype "passive"))
    )
    (net (code "44") (name "unconnected-(D1-IO-3-Pad4)") (class "Default")
      (node (ref "D1") (pin "4") (pinfunction "IO-3_4") (pintype "passive"))
    )
    (net (code "45") (name "unconnected-(D1-IO-4-Pad6)") (class "Default")
      (node (ref "D1") (pin "6") (pinfunction "IO-4_6") (pintype "passive"))
    )
    (net (code "46") (name "unconnected-(J1-ID-Pad4)") (class "Default")
      (node (ref "J1") (pin "4") (pinfunction "ID_4") (pintype "passive"))
    )
    (net (code "47") (name "unconnected-(J10-Pad1)") (class "Default")
      (node (ref "J10") (pin "1") (pinfunction "1_1") (pintype "passive"))
    )
    (net (code "48") (name "unconnected-(J10-Pad8)") (class "Default")
      (node (ref "J10") (pin "8") (pinfunction "8_8") (pintype "passive"))
    )
    (net (code "49") (name "unconnected-(U1-ADC6-Pad19)") (class "Default")
      (node (ref "U1") (pin "19") (pinfunction "ADC6_19") (pintype "bidirectional"))
    )
    (net (code "50") (name "unconnected-(U1-ADC7-Pad22)") (class "Default")
      (node (ref "U1") (pin "22") (pinfunction "ADC7_22") (pintype "bidirectional"))
    )
    (net (code "51") (name "unconnected-(U2-CTS#-Pad9)") (class "Default")
      (node (ref "U2") (pin "9") (pinfunction "CTS#_9") (pintype "passive"))
    )
    (net (code "52") (name "unconnected-(U2-DCD#-Pad12)") (class "Default")
      (node (ref "U2") (pin "12") (pinfunction "DCD#_12") (pintype "passive"))
    )
    (net (code "53") (name "unconnected-(U2-DSR#-Pad10)") (class "Default")
      (node (ref "U2") (pin "10") (pinfunction "DSR#_10") (pintype "passive"))
    )
    (net (code "54") (name "unconnected-(U2-RI#-Pad11)") (class "Default")
      (node (ref "U2") (pin "11") (pinfunction "RI#_11") (pintype "passive"))
    )
    (net (code "55") (name "unconnected-(U2-RS232-Pad15)") (class "Default")
      (node (ref "U2") (pin "15") (pinfunction "RS232_15") (pintype "passive"))
    )
    (net (code "56") (name "unconnected-(U2-RTS#-Pad14)") (class "Default")
      (node (ref "U2") (pin "14") (pinfunction "RTS#_14") (pintype "passive"))
    )
  )
)
